# Sheet1.net
KiCad netlist of a schematic drawn in Altium Designer
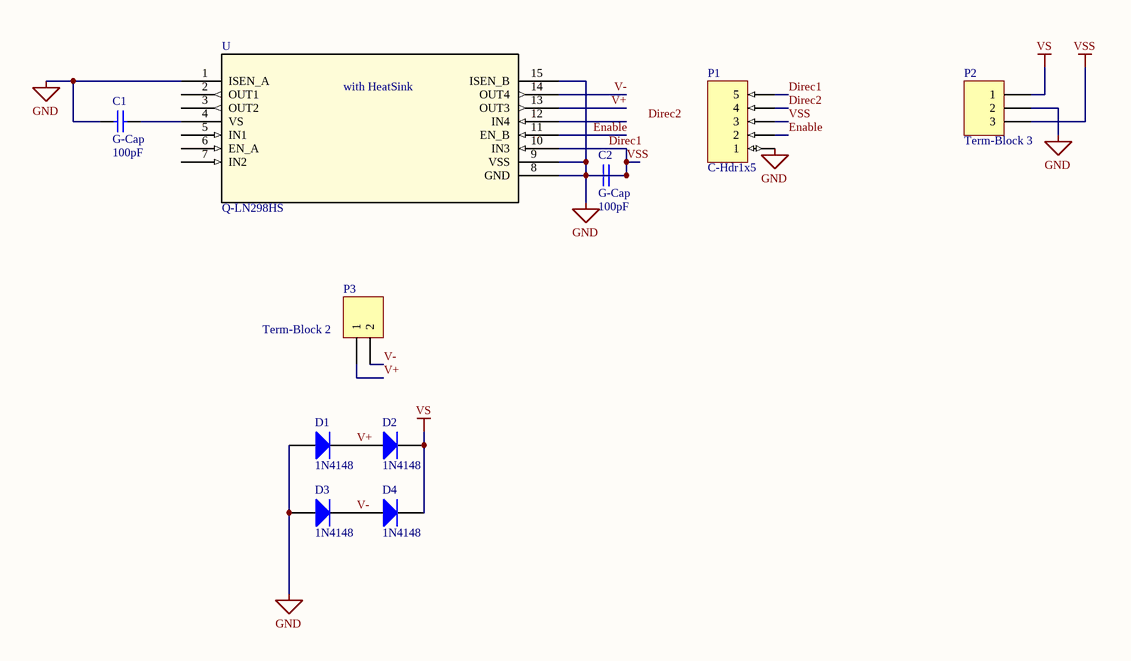
[diagram p0: Sheet1.SchDoc]

(export (version "E")
  (design (tool "Eeschema 10.0.6"))
  (components
    (comp (ref "C1")
      (value "G-Cap")
      (footprint "Cap2.54mm_LGE1.0")
      (description "Capacitor (specify value)")
      (fields (field (name "ALTIUM_VALUE") "100pF") (field (name "PUBLISHER") "Altium Limited"))
      (libsource (lib "PartsDatabaseV16.1") (part "G-Cap"))
    )
    (comp (ref "C2")
      (value "G-Cap")
      (footprint "Cap2.54mm_LGE1.0")
      (description "Capacitor (specify value)")
      (fields (field (name "ALTIUM_VALUE") "100pF") (field (name "PUBLISHER") "Altium Limited"))
      (libsource (lib "PartsDatabaseV16.1") (part "G-Cap"))
    )
    (comp (ref "D1")
      (value "1N4148")
      (footprint "DO-41_XLGE1.2")
      (description "High-speed Diode")
      (libsource (lib "PartsDatabaseV16.1") (part "T-DiodeRect"))
    )
    (comp (ref "D2")
      (value "1N4148")
      (footprint "DO-41_XLGE1.2")
      (description "High-speed Diode")
      (libsource (lib "PartsDatabaseV16.1") (part "T-DiodeRect"))
    )
    (comp (ref "D3")
      (value "1N4148")
      (footprint "DO-41_XLGE1.2")
      (description "High-speed Diode")
      (libsource (lib "PartsDatabaseV16.1") (part "T-DiodeRect"))
    )
    (comp (ref "D4")
      (value "1N4148")
      (footprint "DO-41_XLGE1.2")
      (description "High-speed Diode")
      (libsource (lib "PartsDatabaseV16.1") (part "T-DiodeRect"))
    )
    (comp (ref "P1")
      (value "C-Hdr1x5")
      (footprint "HDR1X5_LGE1.0")
      (description "Header, 6-Pin")
      (fields (field (name "PUBLISHER") "Altium Limited"))
      (libsource (lib "PartsDatabaseV16.1") (part "C-Hdr1x5"))
    )
    (comp (ref "P2")
      (value "Term-Block 3")
      (footprint "TERM-BLOCK-5.08MM-3POS")
      (description "Terminal-Block 1x3")
      (fields (field (name "PUBLISHER") "Altium Limited"))
      (libsource (lib "PartsDatabaseV16.1") (part "C-Block3"))
    )
    (comp (ref "P3")
      (value "Term-Block 2")
      (footprint "TERM-BLOCK-5.08MM-2POS")
      (description "Terminal-Block 1x2")
      (fields (field (name "PUBLISHER") "Altium Limited"))
      (libsource (lib "PartsDatabaseV16.1") (part "C-Block2"))
    )
    (comp (ref "U")
      (value "Q-LN298HS")
      (footprint "Multiwatt15_V_ELEC391HS")
      (description "LN298 - IC Bridge Driver Par 15Multiwatt")
      (fields
        (field (name "MANUFACTURER_PART_NUMBER") "L298N")
        (field (name "COPYRIGHT") "Copyright (C) 2015 Accelerated Designs. All rights reserved")
      )
      (libsource (lib "Additional Parts 391") (part "Q-LN298HS"))
    )
  )
  (nets
    (net (code "1") (name "/Direc2") (class "Default")
      (node (ref "P1") (pin "4") (pinfunction "4_4") (pintype "input"))
    )
    (net (code "2") (name "/Enable") (class "Default")
      (node (ref "P1") (pin "2") (pinfunction "2_2") (pintype "input"))
      (node (ref "U") (pin "11") (pinfunction "EN_B_11") (pintype "input"))
    )
    (net (code "3") (name "/V+") (class "Default")
      (node (ref "D1") (pin "2") (pinfunction "K_2") (pintype "passive"))
      (node (ref "D2") (pin "1") (pinfunction "A_1") (pintype "passive"))
      (node (ref "P3") (pin "1") (pinfunction "1_1") (pintype "passive"))
      (node (ref "U") (pin "13") (pinfunction "OUT3_13") (pintype "output"))
    )
    (net (code "4") (name "/V-") (class "Default")
      (node (ref "D3") (pin "2") (pinfunction "K_2") (pintype "passive"))
      (node (ref "D4") (pin "1") (pinfunction "A_1") (pintype "passive"))
      (node (ref "P3") (pin "2") (pinfunction "2_2") (pintype "passive"))
      (node (ref "U") (pin "14") (pinfunction "OUT4_14") (pintype "output"))
    )
    (net (code "5") (name "GND") (class "Default")
      (node (ref "C1") (pin "1") (pinfunction "1_1") (pintype "passive"))
      (node (ref "C2") (pin "1") (pinfunction "1_1") (pintype "passive"))
      (node (ref "C2") (pin "2") (pinfunction "2_2") (pintype "passive"))
      (node (ref "D1") (pin "1") (pinfunction "A_1") (pintype "passive"))
      (node (ref "D3") (pin "1") (pinfunction "A_1") (pintype "passive"))
      (node (ref "P1") (pin "1") (pinfunction "1_1") (pintype "bidirectional"))
      (node (ref "P1") (pin "3") (pinfunction "3_3") (pintype "input"))
      (node (ref "P1") (pin "5") (pinfunction "5_5") (pintype "input"))
      (node (ref "P2") (pin "2") (pinfunction "2_2") (pintype "passive"))
      (node (ref "P2") (pin "3") (pinfunction "3_3") (pintype "passive"))
      (node (ref "U") (pin "1") (pinfunction "ISEN_A_1") (pintype "passive"))
      (node (ref "U") (pin "10") (pinfunction "IN3_10") (pintype "input"))
      (node (ref "U") (pin "15") (pinfunction "ISEN_B_15") (pintype "passive"))
      (node (ref "U") (pin "8") (pinfunction "GND_8") (pintype "power_in"))
      (node (ref "U") (pin "9") (pinfunction "VSS_9") (pintype "power_in"))
    )
    (net (code "6") (name "Net-(U-VS)") (class "Default")
      (node (ref "C1") (pin "2") (pinfunction "2_2") (pintype "passive"))
      (node (ref "U") (pin "4") (pinfunction "VS_4") (pintype "power_in"))
    )
    (net (code "7") (name "VS") (class "Default")
      (node (ref "D2") (pin "2") (pinfunction "K_2") (pintype "passive"))
      (node (ref "D4") (pin "2") (pinfunction "K_2") (pintype "passive"))
      (node (ref "P2") (pin "1") (pinfunction "1_1") (pintype "passive"))
    )
    (net (code "8") (name "unconnected-(U-EN_A-Pad6)") (class "Default")
      (node (ref "U") (pin "6") (pinfunction "EN_A_6") (pintype "input"))
    )
    (net (code "9") (name "unconnected-(U-IN1-Pad5)") (class "Default")
      (node (ref "U") (pin "5") (pinfunction "IN1_5") (pintype "input"))
    )
    (net (code "10") (name "unconnected-(U-IN2-Pad7)") (class "Default")
      (node (ref "U") (pin "7") (pinfunction "IN2_7") (pintype "input"))
    )
    (net (code "11") (name "unconnected-(U-IN4-Pad12)") (class "Default")
      (node (ref "U") (pin "12") (pinfunction "IN4_12") (pintype "input"))
    )
    (net (code "12") (name "unconnected-(U-OUT1-Pad2)") (class "Default")
      (node (ref "U") (pin "2") (pinfunction "OUT1_2") (pintype "output"))
    )
    (net (code "13") (name "unconnected-(U-OUT2-Pad3)") (class "Default")
      (node (ref "U") (pin "3") (pinfunction "OUT2_3") (pintype "output"))
    )
  )
)
